# H01R0_Backend.net
KiCad netlist of a schematic drawn in Altium Designer
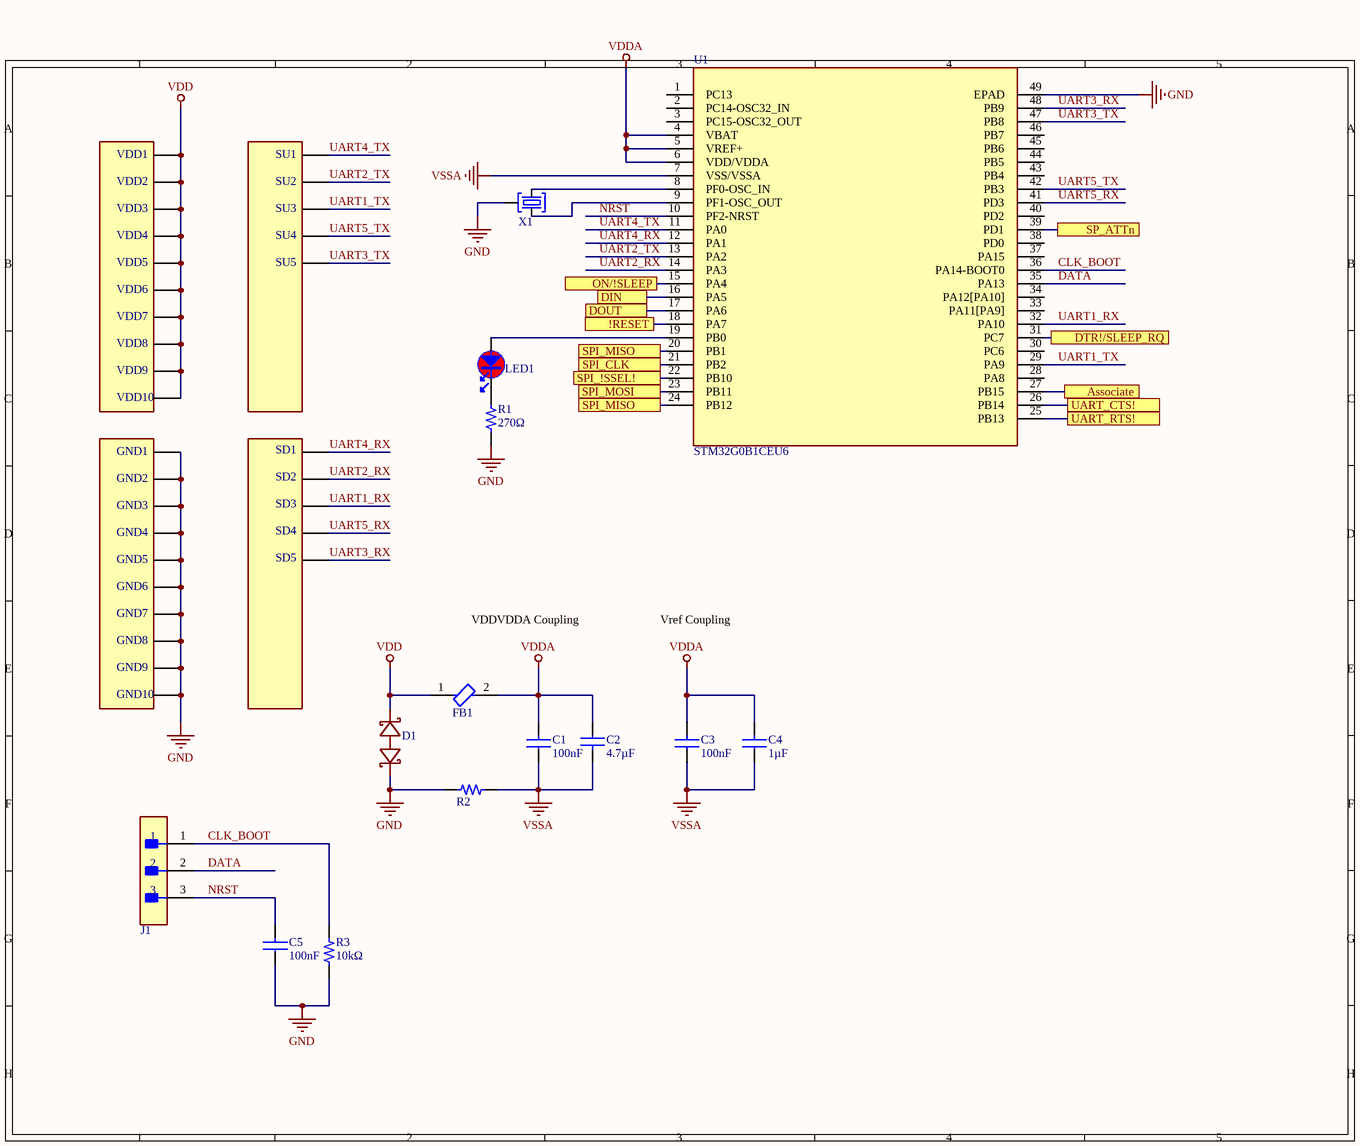
[diagram p0: H01R0_Backend.SchDoc]

(export (version "E")
  (design (tool "Eeschema 10.0.6"))
  (components
    (comp (ref "C1")
      (value "100nF")
      (footprint "C0603")
      (fields
        (field (name "MANUFACTURER") "Samsung Electro-Mechanics")
        (field (name "MANUFACTURER PART NUMBER") "CL10B104KA8NNNC")
        (field (name "TOLERANCE") "10%")
      )
      (libsource (lib "Hexabitz Altium Library") (part "generic Capacitor"))
    )
    (comp (ref "C2")
      (value "4.7µF")
      (footprint "C0805")
      (fields
        (field (name "MANUFACTURER") "Samsung Electro-Mechanics")
        (field (name "MANUFACTURER PART NUMBER") "CL21X475KAQNNNE")
        (field (name "TOLERANCE") "10%")
      )
      (libsource (lib "Hexabitz Altium Library") (part "generic Capacitor"))
    )
    (comp (ref "C3")
      (value "100nF")
      (footprint "C0603")
      (fields
        (field (name "MANUFACTURER") "Samsung Electro-Mechanics")
        (field (name "MANUFACTURER PART NUMBER") "CL10B104KA8NNNC")
        (field (name "TOLERANCE") "10%")
      )
      (libsource (lib "Hexabitz Altium Library") (part "generic Capacitor"))
    )
    (comp (ref "C4")
      (value "1µF")
      (footprint "C0805")
      (description "Ceramic Capacitor, Ceramic, 16V, 10% +Tol, 10% -Tol, X7R, 15% TC, 1uF, Surface Mount, 0805")
      (fields
        (field (name "MANUFACTURER") "Yageo Group")
        (field (name "MANUFACTURER PART NUMBER") "CC0805KKX7R7BB105")
      )
      (libsource (lib "Hexabitz Altium Library") (part "generic Capacitor"))
    )
    (comp (ref "C5")
      (value "100nF")
      (footprint "C0603")
      (fields
        (field (name "MANUFACTURER") "Samsung Electro-Mechanics")
        (field (name "MANUFACTURER PART NUMBER") "CL10B104KA8NNNC")
        (field (name "TOLERANCE") "10%")
      )
      (libsource (lib "Hexabitz Altium Library") (part "generic Capacitor"))
    )
    (comp (ref "D1")
      (value "CDSOD323-T03SC")
      (footprint "SOD2513X114N")
      (description "A 3V, 350W, bi-directional, standard capacitance, SOD323 pkg TVS Diode ¦ Bourns CDSOD323-T03SC")
      (fields (field (name "MANUFACTURER") "Bourns"))
      (libsource (lib "Hexabitz Altium Library") (part "CDSOD323-T03SC"))
    )
    (comp (ref "FB1")
      (value "MMZ1608Y300B")
      (footprint "FP-MMZ1608-0_8-MFG")
      (description "Ferrite Beads 0603 30ohms 1500mA Signal Line AEC-Q200")
      (fields
        (field (name "MANUFACTURER") "TDK")
        (field (name "MANUFACTURER PART NUMBER") "MMZ1608Y300BTD25")
      )
      (libsource (lib "Hexabitz Altium Library") (part "MMZ1608Y300B"))
    )
    (comp (ref "GND1")
      (value "HEXABIT_UART_PORT")
      (footprint "HEXABIT_POWER_PORT_D")
      (libsource (lib "hexabitz_connectors.Library") (part "HEXABIT_POWER_PORT_D"))
    )
    (comp (ref "GND2")
      (value "HEXABIT_UART_PORT")
      (footprint "HEXABIT_POWER_PORT_D")
      (libsource (lib "hexabitz_connectors.Library") (part "HEXABIT_POWER_PORT_D"))
    )
    (comp (ref "GND3")
      (value "HEXABIT_UART_PORT")
      (footprint "HEXABIT_POWER_PORT_D_300R")
      (libsource (lib "hexabitz_connectors.Library") (part "HEXABIT_POWER_PORT_D_300R"))
    )
    (comp (ref "GND4")
      (value "HEXABIT_UART_PORT")
      (footprint "HEXABIT_POWER_PORT_D")
      (libsource (lib "hexabitz_connectors.Library") (part "HEXABIT_POWER_PORT_D"))
    )
    (comp (ref "GND5")
      (value "HEXABIT_UART_PORT")
      (footprint "HEXABIT_POWER_PORT_D")
      (libsource (lib "hexabitz_connectors.Library") (part "HEXABIT_POWER_PORT_D"))
    )
    (comp (ref "GND6")
      (value "HEXABIT_UART_PORT")
      (footprint "HEXABIT_POWER_PORT_D")
      (libsource (lib "hexabitz_connectors.Library") (part "HEXABIT_POWER_PORT_D"))
    )
    (comp (ref "GND7")
      (value "HEXABIT_UART_PORT")
      (footprint "HEXABIT_POWER_PORT_D")
      (libsource (lib "hexabitz_connectors.Library") (part "HEXABIT_POWER_PORT_D"))
    )
    (comp (ref "GND8")
      (value "HEXABIT_UART_PORT")
      (footprint "HEXABIT_POWER_PORT_D_300L")
      (libsource (lib "hexabitz_connectors.Library") (part "HEXABIT_POWER_PORT_D_300L"))
    )
    (comp (ref "GND9")
      (value "HEXABIT_UART_PORT")
      (footprint "HEXABIT_POWER_PORT_D")
      (libsource (lib "hexabitz_connectors.Library") (part "HEXABIT_POWER_PORT_D"))
    )
    (comp (ref "GND10")
      (value "HEXABIT_UART_PORT")
      (footprint "HEXABIT_POWER_PORT_D")
      (libsource (lib "hexabitz_connectors.Library") (part "HEXABIT_POWER_PORT_D"))
    )
    (comp (ref "J1")
      (value "TSW-103-14-G-S")
      (footprint "FP-TSW-103-14-G-S-MFG")
      (description "CONN HEADER VERT 3POS 2.54MM")
      (libsource (lib "Altium Content Vault") (part "cd3439d6ef35ae5d9b27ec4fdd3e828"))
    )
    (comp (ref "LED1")
      (value "VLMS1300-GS08")
      (footprint "FP-6_541-5092_01-4-MFG")
      (description "LED Uni-Color Super Red 639nm 2-Pin Chip 0603(1608Metric) T/R")
      (fields (field (name "MANUFACTURER") "Vishay Semiconductors"))
      (libsource (lib "Hexabitz Altium Library") (part "VLMS1300-GS08"))
    )
    (comp (ref "R1")
      (value "270Ω")
      (footprint "R0603")
      (description "Res Thick Film 0603 270 Ohm 5% 0.1W(1/10W) ±200ppm/C Pad SMD Automotive T/R")
      (fields
        (field (name "MANUFACTURER") "Panasonic")
        (field (name "MANUFACTURER PART NUMBER") "ERJ-3GEYJ271V")
      )
      (libsource (lib "") (part "generic Resistor_1"))
    )
    (comp (ref "R2")
      (value "Manufacturer Part Number")
      (footprint "R0603")
      (libsource (lib "Hexabitz Altium Library") (part "generic Resistor"))
    )
    (comp (ref "R3")
      (value "10kΩ")
      (footprint "R0603")
      (description "100mW Thick Film Resistors ±100ppm/℃ ±1% 10kΩ 0603 Chip Resistor - Surface Mount ROHS")
      (fields
        (field (name "MANUFACTURER") "Yageo Group")
        (field (name "MANUFACTURER PART NUMBER") "RC0603FR-0710KL")
      )
      (libsource (lib "") (part "generic Resistor_2"))
    )
    (comp (ref "SD1")
      (value "HEXABIT_UART_PORT")
      (footprint "HEXABIT_UART_PORT_D")
      (libsource (lib "hexabitz_connectors.Library") (part "HEXABIT_UART_PORT_D"))
    )
    (comp (ref "SD2")
      (value "HEXABIT_UART_PORT")
      (footprint "HEXABIT_UART_PORT_D")
      (libsource (lib "hexabitz_connectors.Library") (part "HEXABIT_UART_PORT_D"))
    )
    (comp (ref "SD3")
      (value "HEXABIT_UART_PORT")
      (footprint "HEXABIT_UART_PORT_D")
      (libsource (lib "hexabitz_connectors.Library") (part "HEXABIT_UART_PORT_D"))
    )
    (comp (ref "SD4")
      (value "HEXABIT_UART_PORT")
      (footprint "HEXABIT_UART_PORT_D")
      (libsource (lib "hexabitz_connectors.Library") (part "HEXABIT_UART_PORT_D"))
    )
    (comp (ref "SD5")
      (value "HEXABIT_UART_PORT")
      (footprint "HEXABIT_UART_PORT_D")
      (libsource (lib "hexabitz_connectors.Library") (part "HEXABIT_UART_PORT_D"))
    )
    (comp (ref "SU1")
      (value "HEXABIT_UART_PORT")
      (footprint "HEXABIT_UART_PORT_U")
      (libsource (lib "hexabitz_connectors.Library") (part "HEXABIT_UART_PORT_U"))
    )
    (comp (ref "SU2")
      (value "HEXABIT_UART_PORT")
      (footprint "HEXABIT_UART_PORT_U")
      (libsource (lib "hexabitz_connectors.Library") (part "HEXABIT_UART_PORT_U"))
    )
    (comp (ref "SU3")
      (value "HEXABIT_UART_PORT")
      (footprint "HEXABIT_UART_PORT_U")
      (libsource (lib "hexabitz_connectors.Library") (part "HEXABIT_UART_PORT_U"))
    )
    (comp (ref "SU4")
      (value "HEXABIT_UART_PORT")
      (footprint "HEXABIT_UART_PORT_U")
      (libsource (lib "hexabitz_connectors.Library") (part "HEXABIT_UART_PORT_U"))
    )
    (comp (ref "SU5")
      (value "HEXABIT_UART_PORT")
      (footprint "HEXABIT_UART_PORT_U")
      (libsource (lib "hexabitz_connectors.Library") (part "HEXABIT_UART_PORT_U"))
    )
    (comp (ref "U1")
      (value "STM32G0B1CEU6")
      (footprint "QFN50P700X700X65-49N-D")
      (description "MCU 32-bit ARM Cortex M0+ RISC 512KB Flash 1.8V/2.5V/3.3V 48-Pin UFQFPN EP Tray")
      (fields
        (field (name "MANUFACTURER") "STMicroelectronics")
        (field (name "MANUFACTURER PART NUMBER") "STM32G0B1CEU6")
      )
      (libsource (lib "Hexabitz Altium Library") (part "STM32G0B1CEU6"))
    )
    (comp (ref "VDD1")
      (value "HEXABIT_UART_PORT")
      (footprint "HEXABIT_POWER_PORT_U")
      (libsource (lib "hexabitz_connectors.Library") (part "HEXABIT_POWER_PORT_U"))
    )
    (comp (ref "VDD2")
      (value "HEXABIT_UART_PORT")
      (footprint "HEXABIT_POWER_PORT_U")
      (libsource (lib "hexabitz_connectors.Library") (part "HEXABIT_POWER_PORT_U"))
    )
    (comp (ref "VDD3")
      (value "HEXABIT_UART_PORT")
      (footprint "HEXABIT_POWER_PORT_U_300R")
      (libsource (lib "hexabitz_connectors.Library") (part "HEXABIT_POWER_PORT_U_300R"))
    )
    (comp (ref "VDD4")
      (value "HEXABIT_UART_PORT")
      (footprint "HEXABIT_POWER_PORT_U")
      (libsource (lib "hexabitz_connectors.Library") (part "HEXABIT_POWER_PORT_U"))
    )
    (comp (ref "VDD5")
      (value "HEXABIT_UART_PORT")
      (footprint "HEXABIT_POWER_PORT_U")
      (libsource (lib "hexabitz_connectors.Library") (part "HEXABIT_POWER_PORT_U"))
    )
    (comp (ref "VDD6")
      (value "HEXABIT_UART_PORT")
      (footprint "HEXABIT_POWER_PORT_U")
      (libsource (lib "hexabitz_connectors.Library") (part "HEXABIT_POWER_PORT_U"))
    )
    (comp (ref "VDD7")
      (value "HEXABIT_UART_PORT")
      (footprint "HEXABIT_POWER_PORT_U")
      (libsource (lib "hexabitz_connectors.Library") (part "HEXABIT_POWER_PORT_U"))
    )
    (comp (ref "VDD8")
      (value "HEXABIT_UART_PORT")
      (footprint "HEXABIT_POWER_PORT_U_300L")
      (libsource (lib "hexabitz_connectors.Library") (part "HEXABIT_POWER_PORT_U_300L"))
    )
    (comp (ref "VDD9")
      (value "HEXABIT_UART_PORT")
      (footprint "HEXABIT_POWER_PORT_U")
      (libsource (lib "hexabitz_connectors.Library") (part "HEXABIT_POWER_PORT_U"))
    )
    (comp (ref "VDD10")
      (value "HEXABIT_UART_PORT")
      (footprint "HEXABIT_POWER_PORT_U")
      (libsource (lib "hexabitz_connectors.Library") (part "HEXABIT_POWER_PORT_U"))
    )
    (comp (ref "X1")
      (value "CSTCE8M00G52Z-R0")
      (footprint "XTALL_CSTCE8M00G52")
      (description "Ceramic Resonator 8MHz ±0.5% (Tol) ±0.2% (Stability) 10pF 40Ohm 3-Pin CSMD T/R")
      (fields (field (name "MANUFACTURER") "Murata") (field (name "TOLERANCE") "0.5%"))
      (libsource (lib "Hexabitz Altium Library") (part "CSTCE8M00G52Z-R0"))
    )
  )
  (nets
    (net (code "1") (name "/!RESET") (class "Default")
      (node (ref "U1") (pin "18") (pinfunction "PA7_18") (pintype "passive"))
    )
    (net (code "2") (name "/Associate") (class "Default")
      (node (ref "U1") (pin "27") (pinfunction "PB15_27") (pintype "passive"))
    )
    (net (code "3") (name "/CLK_BOOT") (class "Default")
      (node (ref "J1") (pin "1") (pinfunction "1_1") (pintype "passive"))
      (node (ref "R3") (pin "1") (pinfunction "1_1") (pintype "passive"))
      (node (ref "U1") (pin "36") (pinfunction "PA14-BOOT0_36") (pintype "passive"))
    )
    (net (code "4") (name "/DATA") (class "Default")
      (node (ref "J1") (pin "2") (pinfunction "2_2") (pintype "passive"))
      (node (ref "U1") (pin "35") (pinfunction "PA13_35") (pintype "passive"))
    )
    (net (code "5") (name "/DIN") (class "Default")
      (node (ref "U1") (pin "16") (pinfunction "PA5_16") (pintype "passive"))
    )
    (net (code "6") (name "/DOUT") (class "Default")
      (node (ref "U1") (pin "17") (pinfunction "PA6_17") (pintype "passive"))
    )
    (net (code "7") (name "/DTR!{slash}SLEEP_RQ") (class "Default")
      (node (ref "U1") (pin "31") (pinfunction "PC7_31") (pintype "passive"))
    )
    (net (code "8") (name "/NRST") (class "Default")
      (node (ref "C5") (pin "2") (pinfunction "2_2") (pintype "passive"))
      (node (ref "J1") (pin "3") (pinfunction "3_3") (pintype "passive"))
      (node (ref "U1") (pin "10") (pinfunction "PF2-NRST_10") (pintype "passive"))
    )
    (net (code "9") (name "/ON{slash}!SLEEP") (class "Default")
      (node (ref "U1") (pin "15") (pinfunction "PA4_15") (pintype "passive"))
    )
    (net (code "10") (name "/SPI_!SSEL!") (class "Default")
      (node (ref "U1") (pin "22") (pinfunction "PB10_22") (pintype "passive"))
    )
    (net (code "11") (name "/SPI_CLK") (class "Default")
      (node (ref "U1") (pin "21") (pinfunction "PB2_21") (pintype "passive"))
    )
    (net (code "12") (name "/SPI_MISO") (class "Default")
      (node (ref "U1") (pin "20") (pinfunction "PB1_20") (pintype "passive"))
      (node (ref "U1") (pin "24") (pinfunction "PB12_24") (pintype "passive"))
    )
    (net (code "13") (name "/SPI_MOSI") (class "Default")
      (node (ref "U1") (pin "23") (pinfunction "PB11_23") (pintype "passive"))
    )
    (net (code "14") (name "/SP_ATTn") (class "Default")
      (node (ref "U1") (pin "39") (pinfunction "PD1_39") (pintype "passive"))
    )
    (net (code "15") (name "/UART1_RX") (class "Default")
      (node (ref "SD3") (pin "UART_D") (pinfunction "UART_D_UART_D") (pintype "passive"))
      (node (ref "U1") (pin "32") (pinfunction "PA10_32") (pintype "passive"))
    )
    (net (code "16") (name "/UART1_TX") (class "Default")
      (node (ref "SU3") (pin "UART_U") (pinfunction "UART_U_UART_U") (pintype "passive"))
      (node (ref "U1") (pin "29") (pinfunction "PA9_29") (pintype "passive"))
    )
    (net (code "17") (name "/UART2_RX") (class "Default")
      (node (ref "SD2") (pin "UART_D") (pinfunction "UART_D_UART_D") (pintype "passive"))
      (node (ref "U1") (pin "14") (pinfunction "PA3_14") (pintype "passive"))
    )
    (net (code "18") (name "/UART2_TX") (class "Default")
      (node (ref "SU2") (pin "UART_U") (pinfunction "UART_U_UART_U") (pintype "passive"))
      (node (ref "U1") (pin "13") (pinfunction "PA2_13") (pintype "passive"))
    )
    (net (code "19") (name "/UART3_RX") (class "Default")
      (node (ref "SD5") (pin "UART_D") (pinfunction "UART_D_UART_D") (pintype "passive"))
      (node (ref "U1") (pin "48") (pinfunction "PB9_48") (pintype "passive"))
    )
    (net (code "20") (name "/UART3_TX") (class "Default")
      (node (ref "SU5") (pin "UART_U") (pinfunction "UART_U_UART_U") (pintype "passive"))
      (node (ref "U1") (pin "47") (pinfunction "PB8_47") (pintype "passive"))
    )
    (net (code "21") (name "/UART4_RX") (class "Default")
      (node (ref "SD1") (pin "UART_D") (pinfunction "UART_D_UART_D") (pintype "passive"))
      (node (ref "U1") (pin "12") (pinfunction "PA1_12") (pintype "passive"))
    )
    (net (code "22") (name "/UART4_TX") (class "Default")
      (node (ref "SU1") (pin "UART_U") (pinfunction "UART_U_UART_U") (pintype "passive"))
      (node (ref "U1") (pin "11") (pinfunction "PA0_11") (pintype "passive"))
    )
    (net (code "23") (name "/UART5_RX") (class "Default")
      (node (ref "SD4") (pin "UART_D") (pinfunction "UART_D_UART_D") (pintype "passive"))
      (node (ref "U1") (pin "41") (pinfunction "PD3_41") (pintype "passive"))
    )
    (net (code "24") (name "/UART5_TX") (class "Default")
      (node (ref "SU4") (pin "UART_U") (pinfunction "UART_U_UART_U") (pintype "passive"))
      (node (ref "U1") (pin "42") (pinfunction "PB3_42") (pintype "passive"))
    )
    (net (code "25") (name "/UART_CTS!") (class "Default")
      (node (ref "U1") (pin "26") (pinfunction "PB14_26") (pintype "passive"))
    )
    (net (code "26") (name "/UART_RTS!") (class "Default")
      (node (ref "U1") (pin "25") (pinfunction "PB13_25") (pintype "passive"))
    )
    (net (code "27") (name "GND") (class "Default")
      (node (ref "C5") (pin "1") (pinfunction "1_1") (pintype "passive"))
      (node (ref "D1") (pin "1") (pinfunction "A_1") (pintype "passive"))
      (node (ref "GND1") (pin "Pwr_D") (pinfunction "Pwr_D_Pwr_D") (pintype "passive"))
      (node (ref "GND10") (pin "Pwr_D") (pinfunction "Pwr_D_Pwr_D") (pintype "passive"))
      (node (ref "GND2") (pin "Pwr_D") (pinfunction "Pwr_D_Pwr_D") (pintype "passive"))
      (node (ref "GND3") (pin "Pwr_D") (pinfunction "Pwr_D_Pwr_D") (pintype "passive"))
      (node (ref "GND4") (pin "Pwr_D") (pinfunction "Pwr_D_Pwr_D") (pintype "passive"))
      (node (ref "GND5") (pin "Pwr_D") (pinfunction "Pwr_D_Pwr_D") (pintype "passive"))
      (node (ref "GND6") (pin "Pwr_D") (pinfunction "Pwr_D_Pwr_D") (pintype "passive"))
      (node (ref "GND7") (pin "Pwr_D") (pinfunction "Pwr_D_Pwr_D") (pintype "passive"))
      (node (ref "GND8") (pin "Pwr_D") (pinfunction "Pwr_D_Pwr_D") (pintype "passive"))
      (node (ref "GND9") (pin "Pwr_D") (pinfunction "Pwr_D_Pwr_D") (pintype "passive"))
      (node (ref "R1") (pin "1") (pinfunction "1_1") (pintype "passive"))
      (node (ref "R2") (pin "1") (pinfunction "1_1") (pintype "passive"))
      (node (ref "R3") (pin "2") (pinfunction "2_2") (pintype "passive"))
      (node (ref "U1") (pin "49") (pinfunction "EPAD_49") (pintype "passive"))
      (node (ref "X1") (pin "P$2") (pinfunction "2_P$2") (pintype "passive"))
    )
    (net (code "28") (name "Net-(LED1-Pad1)") (class "Default")
      (node (ref "LED1") (pin "1") (pintype "passive"))
      (node (ref "R1") (pin "2") (pinfunction "2_2") (pintype "passive"))
    )
    (net (code "29") (name "Net-(U1-PB0)") (class "Default")
      (node (ref "LED1") (pin "2") (pintype "passive"))
      (node (ref "U1") (pin "19") (pinfunction "PB0_19") (pintype "passive"))
    )
    (net (code "30") (name "Net-(U1-PF0-OSC_IN)") (class "Default")
      (node (ref "U1") (pin "8") (pinfunction "PF0-OSC_IN_8") (pintype "passive"))
      (node (ref "X1") (pin "P$3") (pinfunction "3_P$3") (pintype "passive"))
    )
    (net (code "31") (name "Net-(U1-PF1-OSC_OUT)") (class "Default")
      (node (ref "U1") (pin "9") (pinfunction "PF1-OSC_OUT_9") (pintype "passive"))
      (node (ref "X1") (pin "P$1") (pinfunction "1_P$1") (pintype "passive"))
    )
    (net (code "32") (name "VDD") (class "Default")
      (node (ref "D1") (pin "2") (pinfunction "C_2") (pintype "passive"))
      (node (ref "FB1") (pin "1") (pinfunction "1_1") (pintype "passive"))
      (node (ref "VDD1") (pin "Pwr_U") (pinfunction "Pwr_U_Pwr_U") (pintype "passive"))
      (node (ref "VDD10") (pin "Pwr_U") (pinfunction "Pwr_U_Pwr_U") (pintype "passive"))
      (node (ref "VDD2") (pin "Pwr_U") (pinfunction "Pwr_U_Pwr_U") (pintype "passive"))
      (node (ref "VDD3") (pin "Pwr_U") (pinfunction "Pwr_U_Pwr_U") (pintype "passive"))
      (node (ref "VDD4") (pin "Pwr_U") (pinfunction "Pwr_U_Pwr_U") (pintype "passive"))
      (node (ref "VDD5") (pin "Pwr_U") (pinfunction "Pwr_U_Pwr_U") (pintype "passive"))
      (node (ref "VDD6") (pin "Pwr_U") (pinfunction "Pwr_U_Pwr_U") (pintype "passive"))
      (node (ref "VDD7") (pin "Pwr_U") (pinfunction "Pwr_U_Pwr_U") (pintype "passive"))
      (node (ref "VDD8") (pin "Pwr_U") (pinfunction "Pwr_U_Pwr_U") (pintype "passive"))
      (node (ref "VDD9") (pin "Pwr_U") (pinfunction "Pwr_U_Pwr_U") (pintype "passive"))
    )
    (net (code "33") (name "VDDA") (class "Default")
      (node (ref "C1") (pin "2") (pinfunction "2_2") (pintype "passive"))
      (node (ref "C2") (pin "1") (pinfunction "1_1") (pintype "passive"))
      (node (ref "C3") (pin "2") (pinfunction "2_2") (pintype "passive"))
      (node (ref "C4") (pin "2") (pinfunction "2_2") (pintype "passive"))
      (node (ref "FB1") (pin "2") (pinfunction "2_2") (pintype "passive"))
      (node (ref "U1") (pin "4") (pinfunction "VBAT_4") (pintype "passive"))
      (node (ref "U1") (pin "5") (pinfunction "VREF+_5") (pintype "passive"))
      (node (ref "U1") (pin "6") (pinfunction "VDD/VDDA_6") (pintype "passive"))
    )
    (net (code "34") (name "VSSA") (class "Default")
      (node (ref "C1") (pin "1") (pinfunction "1_1") (pintype "passive"))
      (node (ref "C2") (pin "2") (pinfunction "2_2") (pintype "passive"))
      (node (ref "C3") (pin "1") (pinfunction "1_1") (pintype "passive"))
      (node (ref "C4") (pin "1") (pinfunction "1_1") (pintype "passive"))
      (node (ref "R2") (pin "2") (pinfunction "2_2") (pintype "passive"))
      (node (ref "U1") (pin "7") (pinfunction "VSS/VSSA_7") (pintype "passive"))
    )
    (net (code "35") (name "unconnected-(U1-PA8-Pad28)") (class "Default")
      (node (ref "U1") (pin "28") (pinfunction "PA8_28") (pintype "passive"))
    )
    (net (code "36") (name "unconnected-(U1-PA11[PA9]-Pad33)") (class "Default")
      (node (ref "U1") (pin "33") (pinfunction "PA11[PA9]_33") (pintype "passive"))
    )
    (net (code "37") (name "unconnected-(U1-PA12[PA10]-Pad34)") (class "Default")
      (node (ref "U1") (pin "34") (pinfunction "PA12[PA10]_34") (pintype "passive"))
    )
    (net (code "38") (name "unconnected-(U1-PA15-Pad37)") (class "Default")
      (node (ref "U1") (pin "37") (pinfunction "PA15_37") (pintype "passive"))
    )
    (net (code "39") (name "unconnected-(U1-PB4-Pad43)") (class "Default")
      (node (ref "U1") (pin "43") (pinfunction "PB4_43") (pintype "passive"))
    )
    (net (code "40") (name "unconnected-(U1-PB5-Pad44)") (class "Default")
      (node (ref "U1") (pin "44") (pinfunction "PB5_44") (pintype "passive"))
    )
    (net (code "41") (name "unconnected-(U1-PB6-Pad45)") (class "Default")
      (node (ref "U1") (pin "45") (pinfunction "PB6_45") (pintype "passive"))
    )
    (net (code "42") (name "unconnected-(U1-PB7-Pad46)") (class "Default")
      (node (ref "U1") (pin "46") (pinfunction "PB7_46") (pintype "passive"))
    )
    (net (code "43") (name "unconnected-(U1-PC6-Pad30)") (class "Default")
      (node (ref "U1") (pin "30") (pinfunction "PC6_30") (pintype "passive"))
    )
    (net (code "44") (name "unconnected-(U1-PC13-Pad1)") (class "Default")
      (node (ref "U1") (pin "1") (pinfunction "PC13_1") (pintype "passive"))
    )
    (net (code "45") (name "unconnected-(U1-PC14-OSC32_IN-Pad2)") (class "Default")
      (node (ref "U1") (pin "2") (pinfunction "PC14-OSC32_IN_2") (pintype "passive"))
    )
    (net (code "46") (name "unconnected-(U1-PC15-OSC32_OUT-Pad3)") (class "Default")
      (node (ref "U1") (pin "3") (pinfunction "PC15-OSC32_OUT_3") (pintype "passive"))
    )
    (net (code "47") (name "unconnected-(U1-PD0-Pad38)") (class "Default")
      (node (ref "U1") (pin "38") (pinfunction "PD0_38") (pintype "passive"))
    )
    (net (code "48") (name "unconnected-(U1-PD2-Pad40)") (class "Default")
      (node (ref "U1") (pin "40") (pinfunction "PD2_40") (pintype "passive"))
    )
  )
)
